# Schematic.net
KiCad netlist of a schematic drawn in Altium Designer
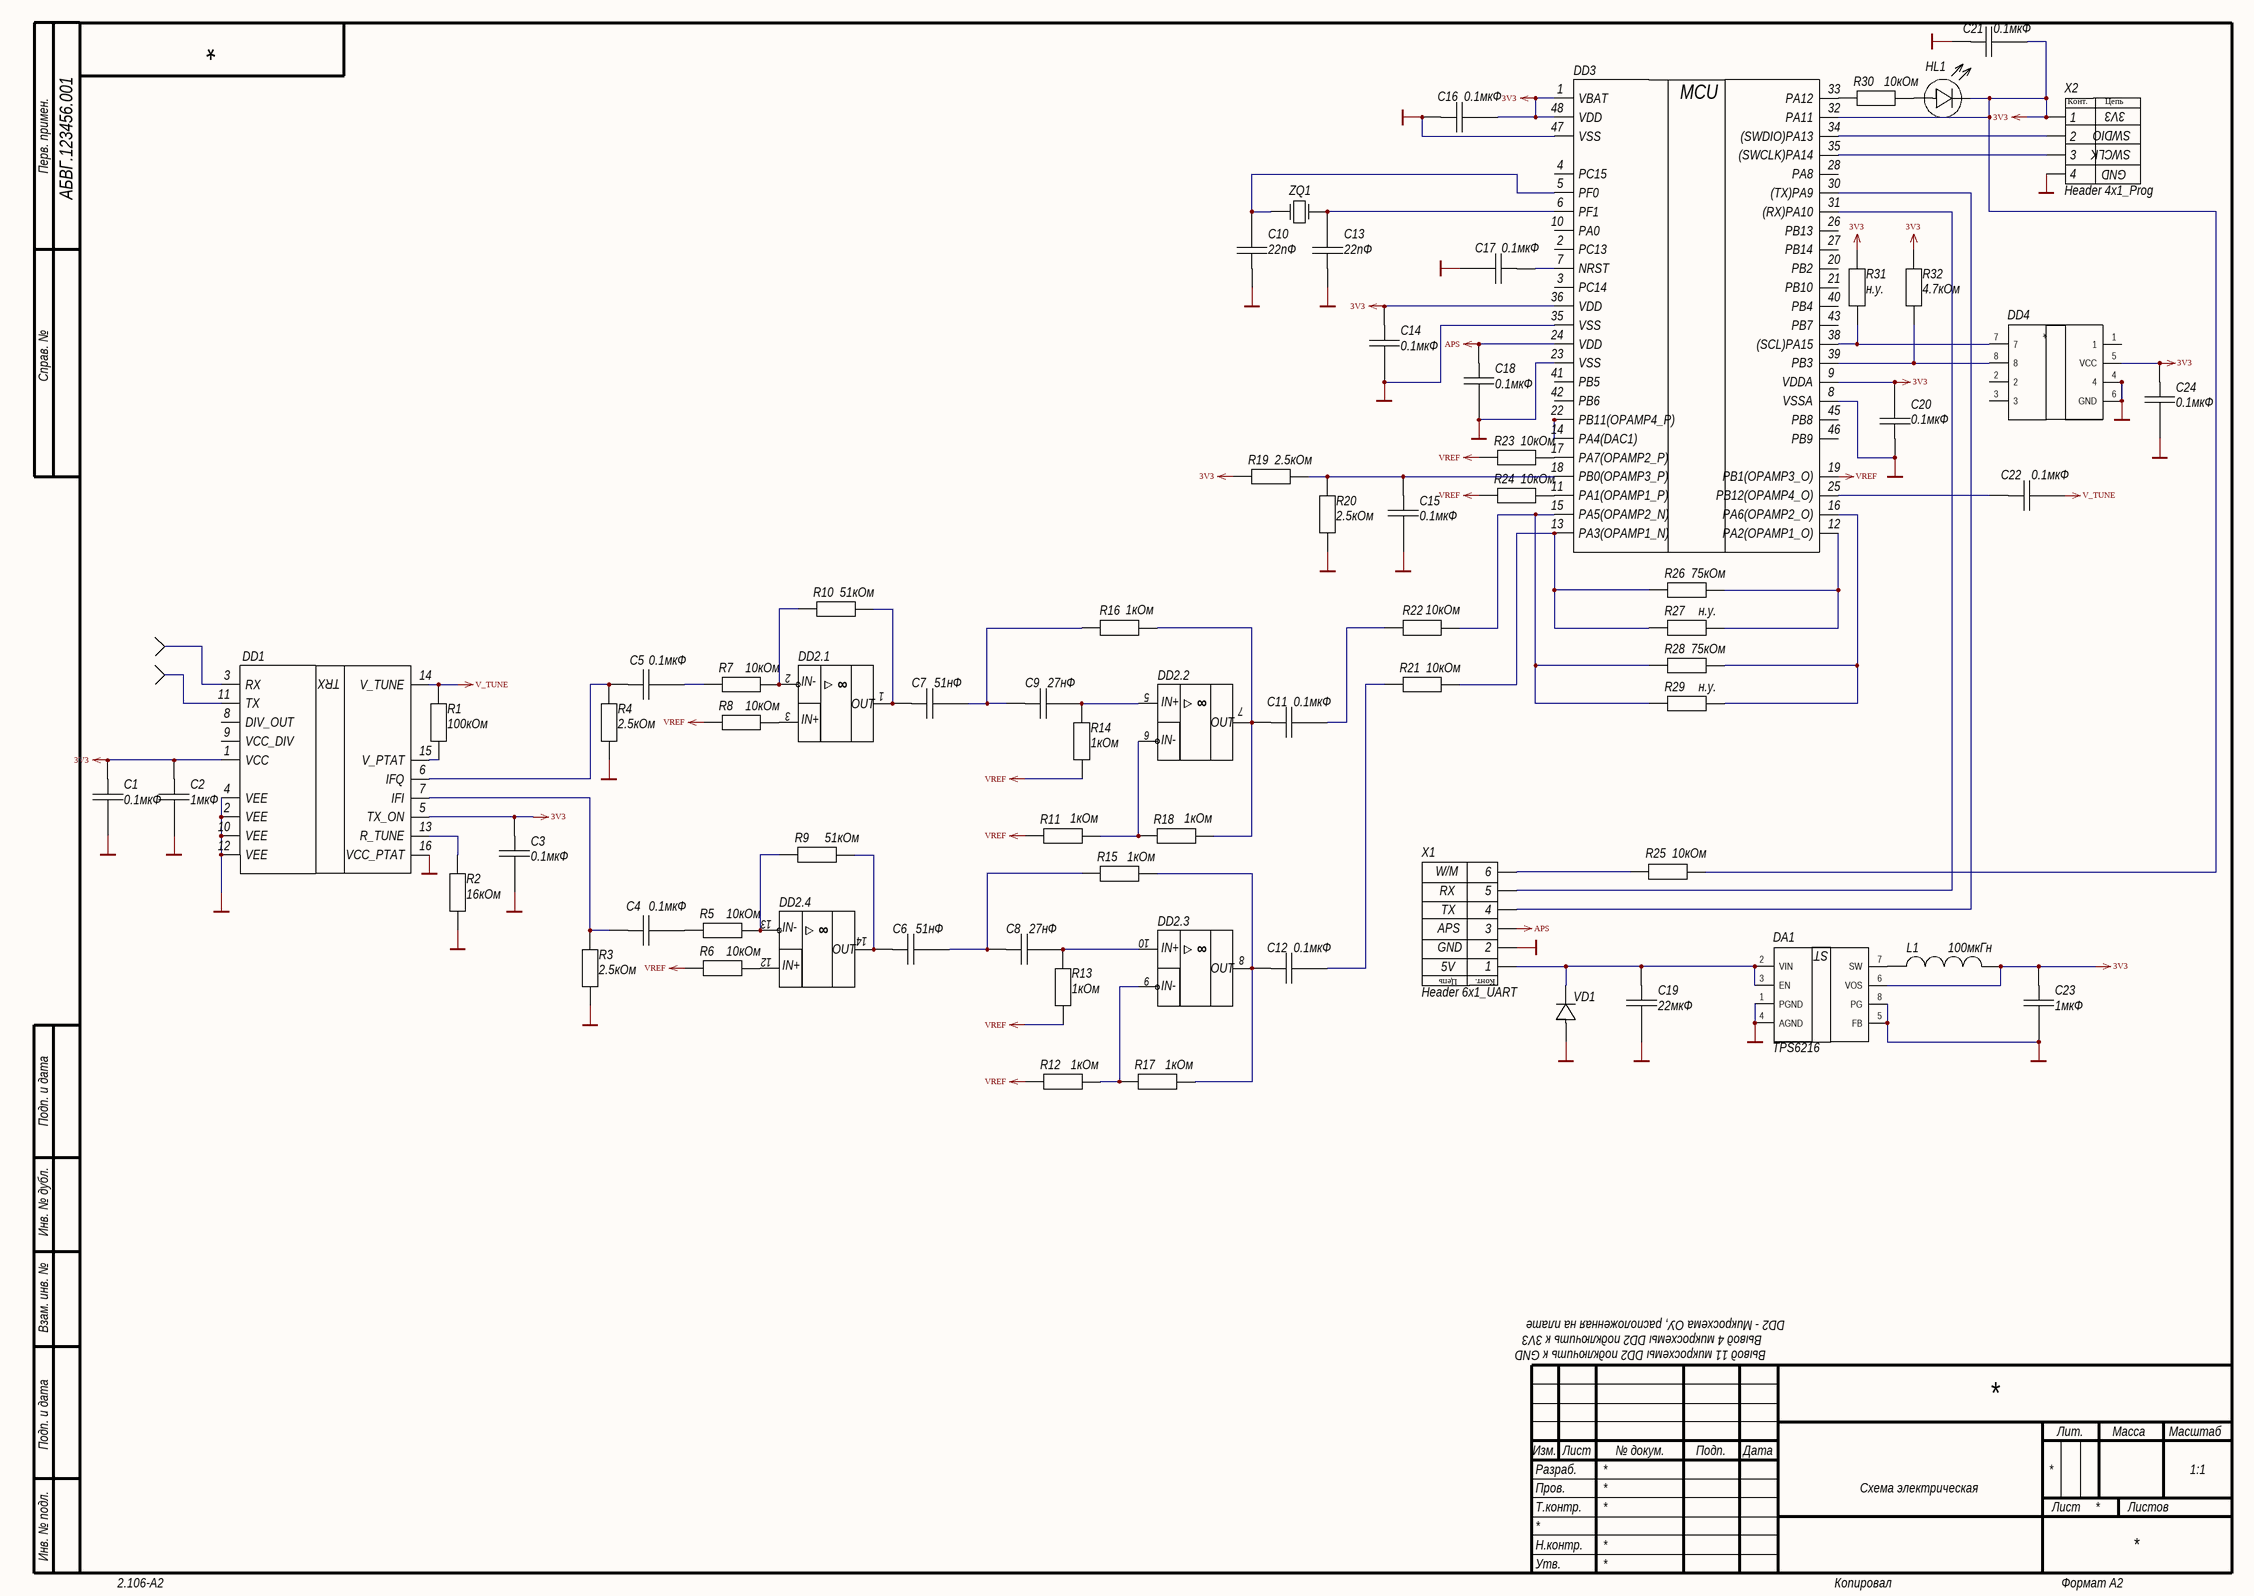
[diagram p0: Schematic.SchDoc]

(export (version "E")
  (design (tool "Eeschema 10.0.6"))
  (components
    (comp (ref "C1") (value "0.1мкФ") (footprint "0805_CAP") (libsource (lib "Schlib1") (part "Capacitor")))
    (comp (ref "C2") (value "1мкФ") (footprint "0805_CAP") (libsource (lib "Schlib1") (part "Capacitor")))
    (comp (ref "C3") (value "0.1мкФ") (footprint "0805_CAP") (libsource (lib "Schlib1") (part "Capacitor")))
    (comp (ref "C4") (value "0.1мкФ") (footprint "0805_CAP") (libsource (lib "Schlib1") (part "Capacitor")))
    (comp (ref "C5") (value "0.1мкФ") (footprint "0805_CAP") (libsource (lib "Schlib1") (part "Capacitor")))
    (comp (ref "C6") (value "51нФ") (footprint "0805_CAP") (libsource (lib "Schlib1") (part "Capacitor")))
    (comp (ref "C7") (value "51нФ") (footprint "0805_CAP") (libsource (lib "Schlib1") (part "Capacitor")))
    (comp (ref "C8") (value "27нФ") (footprint "0805_CAP") (libsource (lib "Schlib1") (part "Capacitor")))
    (comp (ref "C9") (value "27нФ") (footprint "0805_CAP") (libsource (lib "Schlib1") (part "Capacitor")))
    (comp (ref "C10") (value "22пФ") (footprint "0805_CAP") (libsource (lib "Schlib1") (part "Capacitor")))
    (comp (ref "C11") (value "0.1мкФ") (footprint "0805_CAP") (libsource (lib "Schlib1") (part "Capacitor")))
    (comp (ref "C12") (value "0.1мкФ") (footprint "0805_CAP") (libsource (lib "Schlib1") (part "Capacitor")))
    (comp (ref "C13") (value "22пФ") (footprint "0805_CAP") (libsource (lib "Schlib1") (part "Capacitor")))
    (comp (ref "C14") (value "0.1мкФ") (footprint "0805_CAP") (libsource (lib "Schlib1") (part "Capacitor")))
    (comp (ref "C15") (value "0.1мкФ") (footprint "0805_CAP") (libsource (lib "Schlib1") (part "Capacitor")))
    (comp (ref "C16") (value "0.1мкФ") (footprint "0805_CAP") (libsource (lib "Schlib1") (part "Capacitor")))
    (comp (ref "C17") (value "0.1мкФ") (footprint "0805_CAP") (libsource (lib "Schlib1") (part "Capacitor")))
    (comp (ref "C18") (value "0.1мкФ") (footprint "0805_CAP") (libsource (lib "Schlib1") (part "Capacitor")))
    (comp (ref "C19") (value "22мкФ") (footprint "0805_CAP") (libsource (lib "Schlib1") (part "Capacitor")))
    (comp (ref "C20") (value "0.1мкФ") (footprint "0805_CAP") (libsource (lib "Schlib1") (part "Capacitor")))
    (comp (ref "C21") (value "0.1мкФ") (footprint "0805_CAP") (libsource (lib "Schlib1") (part "Capacitor")))
    (comp (ref "C22") (value "0.1мкФ") (footprint "0805_CAP") (libsource (lib "Schlib1") (part "Capacitor")))
    (comp (ref "C23") (value "1мкФ") (footprint "0805_CAP") (libsource (lib "Schlib1") (part "Capacitor")))
    (comp (ref "C24") (value "0.1мкФ") (footprint "0805_CAP") (libsource (lib "Schlib1") (part "Capacitor")))
    (comp (ref "DA1") (value "TPS6216") (libsource (lib "Schlib1") (part "TPS6216")))
    (comp (ref "DD1")
      (value "Infineon")
      (footprint "ULN2803-SOP18")
      (libsource (lib "Schlib1") (part "Infineon"))
    )
    (comp (ref "DD2.1")
      (value "operational amplifier")
      (libsource (lib "Schlib1") (part "operational amplifier"))
    )
    (comp (ref "DD2.2")
      (value "operational amplifier_1")
      (libsource (lib "Schlib1") (part "operational amplifier_1"))
    )
    (comp (ref "DD2.3")
      (value "operational amplifier_1")
      (libsource (lib "Schlib1") (part "operational amplifier_1"))
    )
    (comp (ref "DD2.4")
      (value "operational amplifier")
      (libsource (lib "Schlib1") (part "operational amplifier"))
    )
    (comp (ref "DD3")
      (value "STM32F303")
      (footprint "ATtiny2313-SOP20")
      (libsource (lib "Schlib1") (part "STM32F303"))
    )
    (comp (ref "DD4") (value "Flash_mb") (libsource (lib "Schlib1") (part "Flash_mb")))
    (comp (ref "HL1") (value "LED") (libsource (lib "Schlib1") (part "LED")))
    (comp (ref "L1") (value "100мкГн") (footprint "0603_IND") (libsource (lib "Schlib1") (part "Inductor")))
    (comp (ref "R1") (value "100кОм") (footprint "0805_RES") (libsource (lib "Schlib1") (part "Resistor")))
    (comp (ref "R2") (value "16кОм") (footprint "0805_RES") (libsource (lib "Schlib1") (part "Resistor")))
    (comp (ref "R3") (value "2.5кОм") (footprint "0805_RES") (libsource (lib "Schlib1") (part "Resistor")))
    (comp (ref "R4") (value "2.5кОм") (footprint "0805_RES") (libsource (lib "Schlib1") (part "Resistor")))
    (comp (ref "R5") (value "10кОм") (footprint "0805_RES") (libsource (lib "Schlib1") (part "Resistor")))
    (comp (ref "R6") (value "10кОм") (footprint "0805_RES") (libsource (lib "Schlib1") (part "Resistor")))
    (comp (ref "R7") (value "10кОм") (footprint "0805_RES") (libsource (lib "Schlib1") (part "Resistor")))
    (comp (ref "R8") (value "10кОм") (footprint "0805_RES") (libsource (lib "Schlib1") (part "Resistor")))
    (comp (ref "R9") (value "51кОм") (footprint "0805_RES") (libsource (lib "Schlib1") (part "Resistor")))
    (comp (ref "R10") (value "51кОм") (footprint "0805_RES") (libsource (lib "Schlib1") (part "Resistor")))
    (comp (ref "R11") (value "1кОм") (footprint "0805_RES") (libsource (lib "Schlib1") (part "Resistor")))
    (comp (ref "R12") (value "1кОм") (footprint "0805_RES") (libsource (lib "Schlib1") (part "Resistor")))
    (comp (ref "R13") (value "1кОм") (footprint "0805_RES") (libsource (lib "Schlib1") (part "Resistor")))
    (comp (ref "R14") (value "1кОм") (footprint "0805_RES") (libsource (lib "Schlib1") (part "Resistor")))
    (comp (ref "R15") (value "1кОм") (footprint "0805_RES") (libsource (lib "Schlib1") (part "Resistor")))
    (comp (ref "R16") (value "1кОм") (footprint "0805_RES") (libsource (lib "Schlib1") (part "Resistor")))
    (comp (ref "R17") (value "1кОм") (footprint "0805_RES") (libsource (lib "Schlib1") (part "Resistor")))
    (comp (ref "R18") (value "1кОм") (footprint "0805_RES") (libsource (lib "Schlib1") (part "Resistor")))
    (comp (ref "R19") (value "2.5кОм") (footprint "0805_RES") (libsource (lib "Schlib1") (part "Resistor")))
    (comp (ref "R20") (value "2.5кОм") (footprint "0805_RES") (libsource (lib "Schlib1") (part "Resistor")))
    (comp (ref "R21") (value "10кОм") (footprint "0805_RES") (libsource (lib "Schlib1") (part "Resistor")))
    (comp (ref "R22") (value "10кОм") (footprint "0805_RES") (libsource (lib "Schlib1") (part "Resistor")))
    (comp (ref "R23") (value "10кОм") (footprint "0805_RES") (libsource (lib "Schlib1") (part "Resistor")))
    (comp (ref "R24") (value "10кОм") (footprint "0805_RES") (libsource (lib "Schlib1") (part "Resistor")))
    (comp (ref "R25") (value "10кОм") (footprint "0805_RES") (libsource (lib "Schlib1") (part "Resistor")))
    (comp (ref "R26") (value "75кОм") (footprint "0805_RES") (libsource (lib "Schlib1") (part "Resistor")))
    (comp (ref "R27") (value "н.у.") (footprint "0805_RES") (libsource (lib "Schlib1") (part "Resistor")))
    (comp (ref "R28") (value "75кОм") (footprint "0805_RES") (libsource (lib "Schlib1") (part "Resistor")))
    (comp (ref "R29") (value "н.у.") (footprint "0805_RES") (libsource (lib "Schlib1") (part "Resistor")))
    (comp (ref "R30") (value "10кОм") (footprint "0805_RES") (libsource (lib "Schlib1") (part "Resistor")))
    (comp (ref "R31") (value "н.у.") (footprint "0805_RES") (libsource (lib "Schlib1") (part "Resistor")))
    (comp (ref "R32") (value "4.7кОм") (footprint "0805_RES") (libsource (lib "Schlib1") (part "Resistor")))
    (comp (ref "VD1") (value "diode") (libsource (lib "Schlib1") (part "diode")))
    (comp (ref "X1")
      (value "Header 6x1_UART")
      (footprint "PBS-6")
      (libsource (lib "Schlib1") (part "Header 6x1_UART"))
    )
    (comp (ref "X2")
      (value "Header 4x1_Prog")
      (footprint "PBS-6")
      (libsource (lib "Schlib1") (part "Header 4x1_Prog"))
    )
    (comp (ref "ZQ1") (value "~") (footprint "Quartz") (libsource (lib "Schlib1") (part "Quartz")))
  )
  (nets
    (net (code "1") (name "3V3") (class "Default")
      (node (ref "C1") (pin "2") (pinfunction "2_2") (pintype "passive"))
      (node (ref "C14") (pin "2") (pinfunction "2_2") (pintype "passive"))
      (node (ref "C16") (pin "1") (pinfunction "1_1") (pintype "passive"))
      (node (ref "C2") (pin "2") (pinfunction "2_2") (pintype "passive"))
      (node (ref "C20") (pin "1") (pinfunction "1_1") (pintype "passive"))
      (node (ref "C21") (pin "1") (pinfunction "1_1") (pintype "passive"))
      (node (ref "C23") (pin "2") (pinfunction "2_2") (pintype "passive"))
      (node (ref "C24") (pin "2") (pinfunction "2_2") (pintype "passive"))
      (node (ref "C3") (pin "2") (pinfunction "2_2") (pintype "passive"))
      (node (ref "DA1") (pin "6") (pinfunction "VOS_6") (pintype "passive"))
      (node (ref "DD1") (pin "1") (pinfunction "VCC_1") (pintype "passive"))
      (node (ref "DD1") (pin "5") (pinfunction "TX_ON_5") (pintype "passive"))
      (node (ref "DD3") (pin "1") (pinfunction "VBAT_1") (pintype "passive"))
      (node (ref "DD3") (pin "32") (pinfunction "PA11_32") (pintype "passive"))
      (node (ref "DD3") (pin "36") (pinfunction "VDD_36") (pintype "passive"))
      (node (ref "DD3") (pin "48") (pinfunction "VDD_48") (pintype "passive"))
      (node (ref "DD3") (pin "9") (pinfunction "VDDA_9") (pintype "passive"))
      (node (ref "DD4") (pin "5") (pinfunction "VCC_5") (pintype "passive"))
      (node (ref "HL1") (pin "11") (pinfunction "11_11") (pintype "passive"))
      (node (ref "L1") (pin "2") (pinfunction "2_2") (pintype "passive"))
      (node (ref "R19") (pin "1") (pinfunction "1_1") (pintype "passive"))
      (node (ref "R25") (pin "2") (pinfunction "2_2") (pintype "passive"))
      (node (ref "R31") (pin "1") (pinfunction "1_1") (pintype "passive"))
      (node (ref "R32") (pin "1") (pinfunction "1_1") (pintype "passive"))
      (node (ref "X2") (pin "1") (pinfunction "1_1") (pintype "passive"))
    )
    (net (code "2") (name "APS") (class "Default")
      (node (ref "C18") (pin "2") (pinfunction "2_2") (pintype "passive"))
      (node (ref "DD3") (pin "24") (pinfunction "VDD_24") (pintype "passive"))
      (node (ref "X1") (pin "3") (pinfunction "3_3") (pintype "passive"))
    )
    (net (code "3") (name "GND") (class "Default")
      (node (ref "C1") (pin "1") (pinfunction "1_1") (pintype "passive"))
      (node (ref "C10") (pin "2") (pinfunction "2_2") (pintype "passive"))
      (node (ref "C13") (pin "2") (pinfunction "2_2") (pintype "passive"))
      (node (ref "C14") (pin "1") (pinfunction "1_1") (pintype "passive"))
      (node (ref "C15") (pin "1") (pinfunction "1_1") (pintype "passive"))
      (node (ref "C16") (pin "2") (pinfunction "2_2") (pintype "passive"))
      (node (ref "C17") (pin "1") (pinfunction "1_1") (pintype "passive"))
      (node (ref "C18") (pin "1") (pinfunction "1_1") (pintype "passive"))
      (node (ref "C19") (pin "1") (pinfunction "1_1") (pintype "passive"))
      (node (ref "C2") (pin "1") (pinfunction "1_1") (pintype "passive"))
      (node (ref "C20") (pin "2") (pinfunction "2_2") (pintype "passive"))
      (node (ref "C21") (pin "2") (pinfunction "2_2") (pintype "passive"))
      (node (ref "C23") (pin "1") (pinfunction "1_1") (pintype "passive"))
      (node (ref "C24") (pin "1") (pinfunction "1_1") (pintype "passive"))
      (node (ref "C3") (pin "1") (pinfunction "1_1") (pintype "passive"))
      (node (ref "DA1") (pin "1") (pinfunction "PGND_1") (pintype "passive"))
      (node (ref "DA1") (pin "4") (pinfunction "AGND_4") (pintype "passive"))
      (node (ref "DA1") (pin "5") (pinfunction "FB_5") (pintype "passive"))
      (node (ref "DA1") (pin "8") (pinfunction "PG_8") (pintype "passive"))
      (node (ref "DD1") (pin "10") (pinfunction "VEE_10") (pintype "passive"))
      (node (ref "DD1") (pin "12") (pinfunction "VEE_12") (pintype "passive"))
      (node (ref "DD1") (pin "16") (pinfunction "VCC_PTAT_16") (pintype "passive"))
      (node (ref "DD1") (pin "2") (pinfunction "VEE_2") (pintype "passive"))
      (node (ref "DD1") (pin "4") (pinfunction "VEE_4") (pintype "passive"))
      (node (ref "DD3") (pin "23") (pinfunction "VSS_23") (pintype "passive"))
      (node (ref "DD3") (pin "35") (pinfunction "VSS_35") (pintype "passive"))
      (node (ref "DD3") (pin "47") (pinfunction "VSS_47") (pintype "passive"))
      (node (ref "DD3") (pin "8") (pinfunction "VSSA_8") (pintype "passive"))
      (node (ref "DD4") (pin "4") (pinfunction "4_4") (pintype "passive"))
      (node (ref "DD4") (pin "6") (pinfunction "GND_6") (pintype "passive"))
      (node (ref "R2") (pin "2") (pinfunction "2_2") (pintype "passive"))
      (node (ref "R20") (pin "2") (pinfunction "2_2") (pintype "passive"))
      (node (ref "R3") (pin "2") (pinfunction "2_2") (pintype "passive"))
      (node (ref "R4") (pin "2") (pinfunction "2_2") (pintype "passive"))
      (node (ref "VD1") (pin "10") (pinfunction "10_10") (pintype "passive"))
      (node (ref "X1") (pin "2") (pinfunction "2_2") (pintype "passive"))
      (node (ref "X2") (pin "4") (pinfunction "4_4") (pintype "passive"))
    )
    (net (code "4") (name "Net-(C4-Pad1)") (class "Default")
      (node (ref "C4") (pin "1") (pinfunction "1_1") (pintype "passive"))
      (node (ref "R5") (pin "2") (pinfunction "2_2") (pintype "passive"))
    )
    (net (code "5") (name "Net-(C5-Pad1)") (class "Default")
      (node (ref "C5") (pin "1") (pinfunction "1_1") (pintype "passive"))
      (node (ref "R7") (pin "2") (pinfunction "2_2") (pintype "passive"))
    )
    (net (code "6") (name "Net-(C6-Pad1)") (class "Default")
      (node (ref "C6") (pin "1") (pinfunction "1_1") (pintype "passive"))
      (node (ref "C8") (pin "2") (pinfunction "2_2") (pintype "passive"))
      (node (ref "R15") (pin "2") (pinfunction "2_2") (pintype "passive"))
    )
    (net (code "7") (name "Net-(C6-Pad2)") (class "Default")
      (node (ref "C6") (pin "2") (pinfunction "2_2") (pintype "passive"))
      (node (ref "DD2.4") (pin "9") (pinfunction "9_9") (pintype "passive"))
      (node (ref "R9") (pin "1") (pinfunction "1_1") (pintype "passive"))
    )
    (net (code "8") (name "Net-(C7-Pad1)") (class "Default")
      (node (ref "C7") (pin "1") (pinfunction "1_1") (pintype "passive"))
      (node (ref "C9") (pin "2") (pinfunction "2_2") (pintype "passive"))
      (node (ref "R16") (pin "2") (pinfunction "2_2") (pintype "passive"))
    )
    (net (code "9") (name "Net-(C7-Pad2)") (class "Default")
      (node (ref "C7") (pin "2") (pinfunction "2_2") (pintype "passive"))
      (node (ref "DD2.1") (pin "9") (pinfunction "9_9") (pintype "passive"))
      (node (ref "R10") (pin "1") (pinfunction "1_1") (pintype "passive"))
    )
    (net (code "10") (name "Net-(C8-Pad1)") (class "Default")
      (node (ref "C8") (pin "1") (pinfunction "1_1") (pintype "passive"))
      (node (ref "DD2.3") (pin "7") (pinfunction "7_7") (pintype "passive"))
      (node (ref "R13") (pin "2") (pinfunction "2_2") (pintype "passive"))
    )
    (net (code "11") (name "Net-(C9-Pad1)") (class "Default")
      (node (ref "C9") (pin "1") (pinfunction "1_1") (pintype "passive"))
      (node (ref "DD2.2") (pin "7") (pinfunction "7_7") (pintype "passive"))
      (node (ref "R14") (pin "2") (pinfunction "2_2") (pintype "passive"))
    )
    (net (code "12") (name "Net-(C11-Pad1)") (class "Default")
      (node (ref "C11") (pin "1") (pinfunction "1_1") (pintype "passive"))
      (node (ref "R22") (pin "1") (pinfunction "1_1") (pintype "passive"))
    )
    (net (code "13") (name "Net-(C11-Pad2)") (class "Default")
      (node (ref "C11") (pin "2") (pinfunction "2_2") (pintype "passive"))
      (node (ref "DD2.2") (pin "9") (pinfunction "9_9") (pintype "passive"))
      (node (ref "R16") (pin "1") (pinfunction "1_1") (pintype "passive"))
      (node (ref "R18") (pin "2") (pinfunction "2_2") (pintype "passive"))
    )
    (net (code "14") (name "Net-(C12-Pad1)") (class "Default")
      (node (ref "C12") (pin "1") (pinfunction "1_1") (pintype "passive"))
      (node (ref "R21") (pin "2") (pinfunction "2_2") (pintype "passive"))
    )
    (net (code "15") (name "Net-(C12-Pad2)") (class "Default")
      (node (ref "C12") (pin "2") (pinfunction "2_2") (pintype "passive"))
      (node (ref "DD2.3") (pin "9") (pinfunction "9_9") (pintype "passive"))
      (node (ref "R15") (pin "1") (pinfunction "1_1") (pintype "passive"))
      (node (ref "R17") (pin "2") (pinfunction "2_2") (pintype "passive"))
    )
    (net (code "16") (name "Net-(DA1-EN)") (class "Default")
      (node (ref "C19") (pin "2") (pinfunction "2_2") (pintype "passive"))
      (node (ref "DA1") (pin "2") (pinfunction "VIN_2") (pintype "passive"))
      (node (ref "DA1") (pin "3") (pinfunction "EN_3") (pintype "passive"))
      (node (ref "VD1") (pin "11") (pinfunction "11_11") (pintype "passive"))
      (node (ref "X1") (pin "1") (pinfunction "1_1") (pintype "passive"))
    )
    (net (code "17") (name "Net-(DA1-SW)") (class "Default")
      (node (ref "DA1") (pin "7") (pinfunction "SW_7") (pintype "passive"))
      (node (ref "L1") (pin "1") (pinfunction "1_1") (pintype "passive"))
    )
    (net (code "18") (name "Net-(DD1-IFI)") (class "Default")
      (node (ref "C4") (pin "2") (pinfunction "2_2") (pintype "passive"))
      (node (ref "DD1") (pin "7") (pinfunction "IFI_7") (pintype "passive"))
      (node (ref "R3") (pin "1") (pinfunction "1_1") (pintype "passive"))
    )
    (net (code "19") (name "Net-(DD1-IFQ)") (class "Default")
      (node (ref "C5") (pin "2") (pinfunction "2_2") (pintype "passive"))
      (node (ref "DD1") (pin "6") (pinfunction "IFQ_6") (pintype "passive"))
      (node (ref "R4") (pin "1") (pinfunction "1_1") (pintype "passive"))
    )
    (net (code "20") (name "Net-(DD1-R_TUNE)") (class "Default")
      (node (ref "DD1") (pin "13") (pinfunction "R_TUNE_13") (pintype "passive"))
      (node (ref "R2") (pin "1") (pinfunction "1_1") (pintype "passive"))
    )
    (net (code "21") (name "Net-(DD1-V_PTAT)") (class "Default")
      (node (ref "DD1") (pin "15") (pinfunction "V_PTAT_15") (pintype "passive"))
      (node (ref "R1") (pin "2") (pinfunction "2_2") (pintype "passive"))
    )
    (net (code "22") (name "Net-(DD2.1-Pad7)") (class "Default")
      (node (ref "DD2.1") (pin "7") (pinfunction "7_7") (pintype "passive"))
      (node (ref "R10") (pin "2") (pinfunction "2_2") (pintype "passive"))
      (node (ref "R7") (pin "1") (pinfunction "1_1") (pintype "passive"))
    )
    (net (code "23") (name "Net-(DD2.1-Pad8)") (class "Default")
      (node (ref "DD2.1") (pin "8") (pinfunction "8_8") (pintype "passive"))
      (node (ref "R8") (pin "2") (pinfunction "2_2") (pintype "passive"))
    )
    (net (code "24") (name "Net-(DD2.2-Pad8)") (class "Default")
      (node (ref "DD2.2") (pin "8") (pinfunction "8_8") (pintype "passive"))
      (node (ref "R11") (pin "2") (pinfunction "2_2") (pintype "passive"))
      (node (ref "R18") (pin "1") (pinfunction "1_1") (pintype "passive"))
    )
    (net (code "25") (name "Net-(DD2.3-Pad8)") (class "Default")
      (node (ref "DD2.3") (pin "8") (pinfunction "8_8") (pintype "passive"))
      (node (ref "R12") (pin "2") (pinfunction "2_2") (pintype "passive"))
      (node (ref "R17") (pin "1") (pinfunction "1_1") (pintype "passive"))
    )
    (net (code "26") (name "Net-(DD2.4-Pad7)") (class "Default")
      (node (ref "DD2.4") (pin "7") (pinfunction "7_7") (pintype "passive"))
      (node (ref "R5") (pin "1") (pinfunction "1_1") (pintype "passive"))
      (node (ref "R9") (pin "2") (pinfunction "2_2") (pintype "passive"))
    )
    (net (code "27") (name "Net-(DD2.4-Pad8)") (class "Default")
      (node (ref "DD2.4") (pin "8") (pinfunction "8_8") (pintype "passive"))
      (node (ref "R6") (pin "2") (pinfunction "2_2") (pintype "passive"))
    )
    (net (code "28") (name "Net-(DD3-(RX)PA10)") (class "Default")
      (node (ref "DD3") (pin "31") (pinfunction "(RX)PA10_31") (pintype "passive"))
      (node (ref "X1") (pin "5") (pinfunction "5_5") (pintype "passive"))
    )
    (net (code "29") (name "Net-(DD3-(SCL)PA15)") (class "Default")
      (node (ref "DD3") (pin "38") (pinfunction "(SCL)PA15_38") (pintype "passive"))
      (node (ref "DD4") (pin "7") (pinfunction "7_7") (pintype "passive"))
      (node (ref "R31") (pin "2") (pinfunction "2_2") (pintype "passive"))
    )
    (net (code "30") (name "Net-(DD3-(SWCLK)PA14)") (class "Default")
      (node (ref "DD3") (pin "35") (pinfunction "(SWCLK)PA14_35") (pintype "passive"))
      (node (ref "X2") (pin "3") (pinfunction "3_3") (pintype "passive"))
    )
    (net (code "31") (name "Net-(DD3-(SWDIO)PA13)") (class "Default")
      (node (ref "DD3") (pin "34") (pinfunction "(SWDIO)PA13_34") (pintype "passive"))
      (node (ref "X2") (pin "2") (pinfunction "2_2") (pintype "passive"))
    )
    (net (code "32") (name "Net-(DD3-(TX)PA9)") (class "Default")
      (node (ref "DD3") (pin "30") (pinfunction "(TX)PA9_30") (pintype "passive"))
      (node (ref "X1") (pin "4") (pinfunction "4_4") (pintype "passive"))
    )
    (net (code "33") (name "Net-(DD3-NRST)") (class "Default")
      (node (ref "C17") (pin "2") (pinfunction "2_2") (pintype "passive"))
      (node (ref "DD3") (pin "7") (pinfunction "NRST_7") (pintype "passive"))
    )
    (net (code "34") (name "Net-(DD3-PA1(OPAMP1_P))") (class "Default")
      (node (ref "DD3") (pin "11") (pinfunction "PA1(OPAMP1_P)_11") (pintype "passive"))
      (node (ref "R24") (pin "1") (pinfunction "1_1") (pintype "passive"))
    )
    (net (code "35") (name "Net-(DD3-PA2(OPAMP1_O))") (class "Default")
      (node (ref "DD3") (pin "12") (pinfunction "PA2(OPAMP1_O)_12") (pintype "passive"))
      (node (ref "R26") (pin "1") (pinfunction "1_1") (pintype "passive"))
      (node (ref "R27") (pin "1") (pinfunction "1_1") (pintype "passive"))
    )
    (net (code "36") (name "Net-(DD3-PA3(OPAMP1_N))") (class "Default")
      (node (ref "DD3") (pin "13") (pinfunction "PA3(OPAMP1_N)_13") (pintype "passive"))
      (node (ref "R21") (pin "1") (pinfunction "1_1") (pintype "passive"))
      (node (ref "R26") (pin "2") (pinfunction "2_2") (pintype "passive"))
      (node (ref "R27") (pin "2") (pinfunction "2_2") (pintype "passive"))
    )
    (net (code "37") (name "Net-(DD3-PA4(DAC1))") (class "Default")
      (node (ref "DD3") (pin "14") (pinfunction "PA4(DAC1)_14") (pintype "passive"))
      (node (ref "DD3") (pin "22") (pinfunction "PB11(OPAMP4_P)_22") (pintype "passive"))
    )
    (net (code "38") (name "Net-(DD3-PA5(OPAMP2_N))") (class "Default")
      (node (ref "DD3") (pin "15") (pinfunction "PA5(OPAMP2_N)_15") (pintype "passive"))
      (node (ref "R22") (pin "2") (pinfunction "2_2") (pintype "passive"))
      (node (ref "R28") (pin "2") (pinfunction "2_2") (pintype "passive"))
      (node (ref "R29") (pin "2") (pinfunction "2_2") (pintype "passive"))
    )
    (net (code "39") (name "Net-(DD3-PA6(OPAMP2_O))") (class "Default")
      (node (ref "DD3") (pin "16") (pinfunction "PA6(OPAMP2_O)_16") (pintype "passive"))
      (node (ref "R28") (pin "1") (pinfunction "1_1") (pintype "passive"))
      (node (ref "R29") (pin "1") (pinfunction "1_1") (pintype "passive"))
    )
    (net (code "40") (name "Net-(DD3-PA7(OPAMP2_P))") (class "Default")
      (node (ref "DD3") (pin "17") (pinfunction "PA7(OPAMP2_P)_17") (pintype "passive"))
      (node (ref "R23") (pin "1") (pinfunction "1_1") (pintype "passive"))
    )
    (net (code "41") (name "Net-(DD3-PA12)") (class "Default")
      (node (ref "DD3") (pin "33") (pinfunction "PA12_33") (pintype "passive"))
      (node (ref "R30") (pin "1") (pinfunction "1_1") (pintype "passive"))
    )
    (net (code "42") (name "Net-(DD3-PB0(OPAMP3_P))") (class "Default")
      (node (ref "C15") (pin "2") (pinfunction "2_2") (pintype "passive"))
      (node (ref "DD3") (pin "18") (pinfunction "PB0(OPAMP3_P)_18") (pintype "passive"))
      (node (ref "R19") (pin "2") (pinfunction "2_2") (pintype "passive"))
      (node (ref "R20") (pin "1") (pinfunction "1_1") (pintype "passive"))
    )
    (net (code "43") (name "Net-(DD3-PB3)") (class "Default")
      (node (ref "DD3") (pin "39") (pinfunction "PB3_39") (pintype "passive"))
      (node (ref "DD4") (pin "8") (pinfunction "8_8") (pintype "passive"))
      (node (ref "R32") (pin "2") (pinfunction "2_2") (pintype "passive"))
    )
    (net (code "44") (name "Net-(DD3-PB12(OPAMP4_O))") (class "Default")
      (node (ref "C22") (pin "2") (pinfunction "2_2") (pintype "passive"))
      (node (ref "DD3") (pin "25") (pinfunction "PB12(OPAMP4_O)_25") (pintype "passive"))
    )
    (net (code "45") (name "Net-(DD3-PF0)") (class "Default")
      (node (ref "C10") (pin "1") (pinfunction "1_1") (pintype "passive"))
      (node (ref "DD3") (pin "5") (pinfunction "PF0_5") (pintype "passive"))
      (node (ref "ZQ1") (pin "2") (pinfunction "2_2") (pintype "passive"))
    )
    (net (code "46") (name "Net-(DD3-PF1)") (class "Default")
      (node (ref "C13") (pin "1") (pinfunction "1_1") (pintype "passive"))
      (node (ref "DD3") (pin "6") (pinfunction "PF1_6") (pintype "passive"))
      (node (ref "ZQ1") (pin "1") (pinfunction "1_1") (pintype "passive"))
    )
    (net (code "47") (name "Net-(HL1-Pad10)") (class "Default")
      (node (ref "HL1") (pin "10") (pinfunction "10_10") (pintype "passive"))
      (node (ref "R30") (pin "2") (pinfunction "2_2") (pintype "passive"))
    )
    (net (code "48") (name "Net-(R25-Pad1)") (class "Default")
      (node (ref "R25") (pin "1") (pinfunction "1_1") (pintype "passive"))
      (node (ref "X1") (pin "6") (pinfunction "6_6") (pintype "passive"))
    )
    (net (code "49") (name "VREF") (class "Default")
      (node (ref "DD3") (pin "19") (pinfunction "PB1(OPAMP3_O)_19") (pintype "passive"))
      (node (ref "R11") (pin "1") (pinfunction "1_1") (pintype "passive"))
      (node (ref "R12") (pin "1") (pinfunction "1_1") (pintype "passive"))
      (node (ref "R13") (pin "1") (pinfunction "1_1") (pintype "passive"))
      (node (ref "R14") (pin "1") (pinfunction "1_1") (pintype "passive"))
      (node (ref "R23") (pin "2") (pinfunction "2_2") (pintype "passive"))
      (node (ref "R24") (pin "2") (pinfunction "2_2") (pintype "passive"))
      (node (ref "R6") (pin "1") (pinfunction "1_1") (pintype "passive"))
      (node (ref "R8") (pin "1") (pinfunction "1_1") (pintype "passive"))
    )
    (net (code "50") (name "V_TUNE") (class "Default")
      (node (ref "C22") (pin "1") (pinfunction "1_1") (pintype "passive"))
      (node (ref "DD1") (pin "14") (pinfunction "V_TUNE_14") (pintype "passive"))
      (node (ref "R1") (pin "1") (pinfunction "1_1") (pintype "passive"))
    )
    (net (code "51") (name "unconnected-(DD1-DIV_OUT-Pad8)") (class "Default")
      (node (ref "DD1") (pin "8") (pinfunction "DIV_OUT_8") (pintype "passive"))
    )
    (net (code "52") (name "unconnected-(DD1-RX-Pad3)") (class "Default")
      (node (ref "DD1") (pin "3") (pinfunction "RX_3") (pintype "passive"))
    )
    (net (code "53") (name "unconnected-(DD1-TX-Pad11)") (class "Default")
      (node (ref "DD1") (pin "11") (pinfunction "TX_11") (pintype "passive"))
    )
    (net (code "54") (name "unconnected-(DD1-VCC_DIV-Pad9)") (class "Default")
      (node (ref "DD1") (pin "9") (pinfunction "VCC_DIV_9") (pintype "passive"))
    )
    (net (code "55") (name "unconnected-(DD3-PA0-Pad10)") (class "Default")
      (node (ref "DD3") (pin "10") (pinfunction "PA0_10") (pintype "passive"))
    )
    (net (code "56") (name "unconnected-(DD3-PA8-Pad28)") (class "Default")
      (node (ref "DD3") (pin "28") (pinfunction "PA8_28") (pintype "passive"))
    )
    (net (code "57") (name "unconnected-(DD3-PB2-Pad20)") (class "Default")
      (node (ref "DD3") (pin "20") (pinfunction "PB2_20") (pintype "passive"))
    )
    (net (code "58") (name "unconnected-(DD3-PB4-Pad40)") (class "Default")
      (node (ref "DD3") (pin "40") (pinfunction "PB4_40") (pintype "passive"))
    )
    (net (code "59") (name "unconnected-(DD3-PB5-Pad41)") (class "Default")
      (node (ref "DD3") (pin "41") (pinfunction "PB5_41") (pintype "passive"))
    )
    (net (code "60") (name "unconnected-(DD3-PB6-Pad42)") (class "Default")
      (node (ref "DD3") (pin "42") (pinfunction "PB6_42") (pintype "passive"))
    )
    (net (code "61") (name "unconnected-(DD3-PB7-Pad43)") (class "Default")
      (node (ref "DD3") (pin "43") (pinfunction "PB7_43") (pintype "passive"))
    )
    (net (code "62") (name "unconnected-(DD3-PB8-Pad45)") (class "Default")
      (node (ref "DD3") (pin "45") (pinfunction "PB8_45") (pintype "passive"))
    )
    (net (code "63") (name "unconnected-(DD3-PB9-Pad46)") (class "Default")
      (node (ref "DD3") (pin "46") (pinfunction "PB9_46") (pintype "passive"))
    )
    (net (code "64") (name "unconnected-(DD3-PB10-Pad21)") (class "Default")
      (node (ref "DD3") (pin "21") (pinfunction "PB10_21") (pintype "passive"))
    )
    (net (code "65") (name "unconnected-(DD3-PB13-Pad26)") (class "Default")
      (node (ref "DD3") (pin "26") (pinfunction "PB13_26") (pintype "passive"))
    )
    (net (code "66") (name "unconnected-(DD3-PB14-Pad27)") (class "Default")
      (node (ref "DD3") (pin "27") (pinfunction "PB14_27") (pintype "passive"))
    )
    (net (code "67") (name "unconnected-(DD3-PC13-Pad2)") (class "Default")
      (node (ref "DD3") (pin "2") (pinfunction "PC13_2") (pintype "passive"))
    )
    (net (code "68") (name "unconnected-(DD3-PC14-Pad3)") (class "Default")
      (node (ref "DD3") (pin "3") (pinfunction "PC14_3") (pintype "passive"))
    )
    (net (code "69") (name "unconnected-(DD3-PC15-Pad4)") (class "Default")
      (node (ref "DD3") (pin "4") (pinfunction "PC15_4") (pintype "passive"))
    )
    (net (code "70") (name "unconnected-(DD4-Pad1)") (class "Default")
      (node (ref "DD4") (pin "1") (pinfunction "1_1") (pintype "passive"))
    )
    (net (code "71") (name "unconnected-(DD4-Pad2)") (class "Default")
      (node (ref "DD4") (pin "2") (pinfunction "2_2") (pintype "passive"))
    )
    (net (code "72") (name "unconnected-(DD4-Pad3)") (class "Default")
      (node (ref "DD4") (pin "3") (pinfunction "3_3") (pintype "passive"))
    )
  )
)
